# Microcontroller.net
KiCad netlist of a schematic drawn in Altium Designer
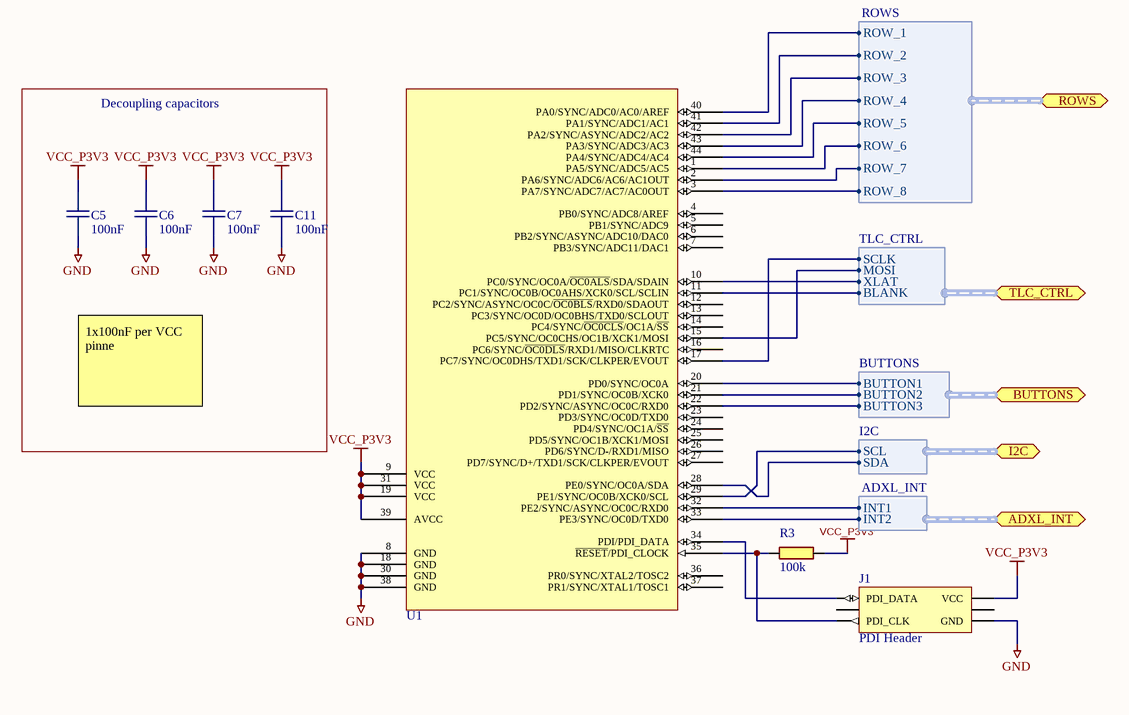
[diagram p0: Microcontroller.SchDoc]

(export (version "E")
  (design (tool "Eeschema 10.0.6"))
  (components
    (comp (ref "C5")
      (value "100nF")
      (footprint "CAPC0805(2012)100_N")
      (description "X7R 50V")
      (libsource (lib "OVLib") (part "CAP"))
    )
    (comp (ref "C6")
      (value "100nF")
      (footprint "CAPC0805(2012)100_N")
      (description "X7R 50V")
      (libsource (lib "OVLib") (part "CAP"))
    )
    (comp (ref "C7")
      (value "100nF")
      (footprint "CAPC0805(2012)100_N")
      (description "X7R 50V")
      (libsource (lib "OVLib") (part "CAP"))
    )
    (comp (ref "C11")
      (value "100nF")
      (footprint "CAPC0805(2012)100_N")
      (description "X7R 50V")
      (libsource (lib "OVLib") (part "CAP"))
    )
    (comp (ref "J1")
      (value "PDI Header")
      (footprint "HEADER_3x2")
      (description "PDI Xmega programming header")
      (libsource (lib "OVLib") (part "PDI-HEADER"))
    )
    (comp (ref "R3")
      (value "100k")
      (footprint "RESC0603(1608)_N")
      (description "0.1W 1% Thick film resistor")
      (libsource (lib "OVLib") (part "Resistor2"))
    )
    (comp (ref "U1")
      (value "ATXMEGA-A4U")
      (footprint "TQFP80P1200X1200X120-44N")
      (libsource (lib "OVLib") (part "ATXMEGA-A4U"))
    )
  )
  (nets
    (net (code "6") (name "/BLANK") (class "Default")
      (node (ref "U1") (pin "11") (pinfunction "PC1/SYNC/OC0B/OC0AHS/XCK0/SCL/SCLIN_11") (pintype "bidirectional"))
    )
    (net (code "7") (name "/BUTTON1") (class "Default")
      (node (ref "U1") (pin "20") (pinfunction "PD0/SYNC/OC0A_20") (pintype "bidirectional"))
    )
    (net (code "8") (name "/BUTTON2") (class "Default")
      (node (ref "U1") (pin "21") (pinfunction "PD1/SYNC/OC0B/XCK0_21") (pintype "bidirectional"))
    )
    (net (code "9") (name "/BUTTON3") (class "Default")
      (node (ref "U1") (pin "22") (pinfunction "PD2/SYNC/ASYNC/OC0C/RXD0_22") (pintype "bidirectional"))
    )
    (net (code "10") (name "/INT1") (class "Default")
      (node (ref "U1") (pin "32") (pinfunction "PE2/SYNC/ASYNC/OC0C/RXD0_32") (pintype "bidirectional"))
    )
    (net (code "11") (name "/INT2") (class "Default")
      (node (ref "U1") (pin "33") (pinfunction "PE3/SYNC/OC0D/TXD0_33") (pintype "bidirectional"))
    )
    (net (code "12") (name "/MOSI") (class "Default")
      (node (ref "U1") (pin "15") (pinfunction "PC5/SYNC/OC0CHS/OC1B/XCK1/MOSI_15") (pintype "bidirectional"))
    )
    (net (code "13") (name "/ROW_1") (class "Default")
      (node (ref "U1") (pin "40") (pinfunction "PA0/SYNC/ADC0/AC0/AREF_40") (pintype "bidirectional"))
    )
    (net (code "14") (name "/ROW_2") (class "Default")
      (node (ref "U1") (pin "41") (pinfunction "PA1/SYNC/ADC1/AC1_41") (pintype "bidirectional"))
    )
    (net (code "15") (name "/ROW_3") (class "Default")
      (node (ref "U1") (pin "42") (pinfunction "PA2/SYNC/ASYNC/ADC2/AC2_42") (pintype "bidirectional"))
    )
    (net (code "16") (name "/ROW_4") (class "Default")
      (node (ref "U1") (pin "43") (pinfunction "PA3/SYNC/ADC3/AC3_43") (pintype "bidirectional"))
    )
    (net (code "17") (name "/ROW_5") (class "Default")
      (node (ref "U1") (pin "44") (pinfunction "PA4/SYNC/ADC4/AC4_44") (pintype "bidirectional"))
    )
    (net (code "18") (name "/ROW_6") (class "Default")
      (node (ref "U1") (pin "1") (pinfunction "PA5/SYNC/ADC5/AC5_1") (pintype "bidirectional"))
    )
    (net (code "19") (name "/ROW_7") (class "Default")
      (node (ref "U1") (pin "2") (pinfunction "PA6/SYNC/ADC6/AC6/AC1OUT_2") (pintype "bidirectional"))
    )
    (net (code "20") (name "/ROW_8") (class "Default")
      (node (ref "U1") (pin "3") (pinfunction "PA7/SYNC/ADC7/AC7/AC0OUT_3") (pintype "bidirectional"))
    )
    (net (code "21") (name "/SCL") (class "Default")
      (node (ref "U1") (pin "29") (pinfunction "PE1/SYNC/OC0B/XCK0/SCL_29") (pintype "bidirectional"))
    )
    (net (code "22") (name "/SCLK") (class "Default")
      (node (ref "U1") (pin "17") (pinfunction "PC7/SYNC/OC0DHS/TXD1/SCK/CLKPER/EVOUT_17") (pintype "bidirectional"))
    )
    (net (code "23") (name "/SDA") (class "Default")
      (node (ref "U1") (pin "28") (pinfunction "PE0/SYNC/OC0A/SDA_28") (pintype "bidirectional"))
    )
    (net (code "24") (name "/XLAT") (class "Default")
      (node (ref "U1") (pin "10") (pinfunction "PC0/SYNC/OC0A/~{OC0ALS}/SDA/SDAIN_10") (pintype "bidirectional"))
    )
    (net (code "30") (name "GND") (class "Default")
      (node (ref "C11") (pin "1") (pinfunction "1_1") (pintype "passive"))
      (node (ref "C5") (pin "1") (pinfunction "1_1") (pintype "passive"))
      (node (ref "C6") (pin "1") (pinfunction "1_1") (pintype "passive"))
      (node (ref "C7") (pin "1") (pinfunction "1_1") (pintype "passive"))
      (node (ref "J1") (pin "6") (pinfunction "GND_6") (pintype "power_in"))
      (node (ref "U1") (pin "18") (pinfunction "GND_18") (pintype "power_in"))
      (node (ref "U1") (pin "30") (pinfunction "GND_30") (pintype "power_in"))
      (node (ref "U1") (pin "38") (pinfunction "GND_38") (pintype "power_in"))
      (node (ref "U1") (pin "8") (pinfunction "GND_8") (pintype "power_in"))
    )
    (net (code "31") (name "Net-(J1-PDI_CLK)") (class "Default")
      (node (ref "J1") (pin "5") (pinfunction "PDI_CLK_5") (pintype "output"))
      (node (ref "R3") (pin "2") (pinfunction "2_2") (pintype "passive"))
      (node (ref "U1") (pin "35") (pinfunction "~{RESET}/PDI_CLOCK_35") (pintype "input"))
    )
    (net (code "32") (name "Net-(J1-PDI_DATA)") (class "Default")
      (node (ref "J1") (pin "1") (pinfunction "PDI_DATA_1") (pintype "bidirectional"))
      (node (ref "U1") (pin "34") (pinfunction "PDI/PDI_DATA_34") (pintype "bidirectional"))
    )
    (net (code "33") (name "VCC_P3V3") (class "Default")
      (node (ref "C11") (pin "2") (pinfunction "2_2") (pintype "passive"))
      (node (ref "C5") (pin "2") (pinfunction "2_2") (pintype "passive"))
      (node (ref "C6") (pin "2") (pinfunction "2_2") (pintype "passive"))
      (node (ref "C7") (pin "2") (pinfunction "2_2") (pintype "passive"))
      (node (ref "J1") (pin "2") (pinfunction "VCC_2") (pintype "power_in"))
      (node (ref "R3") (pin "1") (pinfunction "1_1") (pintype "passive"))
      (node (ref "U1") (pin "19") (pinfunction "VCC_19") (pintype "power_in"))
      (node (ref "U1") (pin "31") (pinfunction "VCC_31") (pintype "power_in"))
      (node (ref "U1") (pin "39") (pinfunction "AVCC_39") (pintype "power_in"))
      (node (ref "U1") (pin "9") (pinfunction "VCC_9") (pintype "power_in"))
    )
    (net (code "34") (name "unconnected-(J1-Pad3)") (class "Default")
      (node (ref "J1") (pin "3") (pinfunction "3_3") (pintype "passive"))
    )
    (net (code "35") (name "unconnected-(J1-Pad4)") (class "Default")
      (node (ref "J1") (pin "4") (pinfunction "4_4") (pintype "passive"))
    )
    (net (code "36") (name "unconnected-(U1-PB0{slash}SYNC{slash}ADC8{slash}AREF-Pad4)") (class "Default")
      (node (ref "U1") (pin "4") (pinfunction "PB0/SYNC/ADC8/AREF_4") (pintype "bidirectional"))
    )
    (net (code "37") (name "unconnected-(U1-PB1{slash}SYNC{slash}ADC9-Pad5)") (class "Default")
      (node (ref "U1") (pin "5") (pinfunction "PB1/SYNC/ADC9_5") (pintype "bidirectional"))
    )
    (net (code "38") (name "unconnected-(U1-PB2{slash}SYNC{slash}ASYNC{slash}ADC10{slash}DAC0-Pad6)") (class "Default")
      (node (ref "U1") (pin "6") (pinfunction "PB2/SYNC/ASYNC/ADC10/DAC0_6") (pintype "bidirectional"))
    )
    (net (code "39") (name "unconnected-(U1-PB3{slash}SYNC{slash}ADC11{slash}DAC1-Pad7)") (class "Default")
      (node (ref "U1") (pin "7") (pinfunction "PB3/SYNC/ADC11/DAC1_7") (pintype "bidirectional"))
    )
    (net (code "40") (name "unconnected-(U1-PC2{slash}SYNC{slash}ASYNC{slash}OC0C{slash}~{OC0BLS}{slash}RXD0{slash}SDAOUT-Pad12)") (class "Default")
      (node (ref "U1") (pin "12") (pinfunction "PC2/SYNC/ASYNC/OC0C/~{OC0BLS}/RXD0/SDAOUT_12") (pintype "bidirectional"))
    )
    (net (code "41") (name "unconnected-(U1-PC3{slash}SYNC{slash}OC0D{slash}OC0BHS{slash}TXD0{slash}SCLOUT-Pad13)") (class "Default")
      (node (ref "U1") (pin "13") (pinfunction "PC3/SYNC/OC0D/OC0BHS/TXD0/SCLOUT_13") (pintype "bidirectional"))
    )
    (net (code "42") (name "unconnected-(U1-PC4{slash}SYNC{slash}~{OC0CLS}{slash}OC1A{slash}~{SS}-Pad14)") (class "Default")
      (node (ref "U1") (pin "14") (pinfunction "PC4/SYNC/~{OC0CLS}/OC1A/~{SS}_14") (pintype "bidirectional"))
    )
    (net (code "43") (name "unconnected-(U1-PC6{slash}SYNC{slash}~{OC0DLS}{slash}RXD1{slash}MISO{slash}CLKRTC-Pad16)") (class "Default")
      (node (ref "U1") (pin "16") (pinfunction "PC6/SYNC/~{OC0DLS}/RXD1/MISO/CLKRTC_16") (pintype "bidirectional"))
    )
    (net (code "44") (name "unconnected-(U1-PD3{slash}SYNC{slash}OC0D{slash}TXD0-Pad23)") (class "Default")
      (node (ref "U1") (pin "23") (pinfunction "PD3/SYNC/OC0D/TXD0_23") (pintype "bidirectional"))
    )
    (net (code "45") (name "unconnected-(U1-PD4{slash}SYNC{slash}OC1A{slash}~{SS}-Pad24)") (class "Default")
      (node (ref "U1") (pin "24") (pinfunction "PD4/SYNC/OC1A/~{SS}_24") (pintype "bidirectional"))
    )
    (net (code "46") (name "unconnected-(U1-PD5{slash}SYNC{slash}OC1B{slash}XCK1{slash}MOSI-Pad25)") (class "Default")
      (node (ref "U1") (pin "25") (pinfunction "PD5/SYNC/OC1B/XCK1/MOSI_25") (pintype "bidirectional"))
    )
    (net (code "47") (name "unconnected-(U1-PD6{slash}SYNC{slash}D-{slash}RXD1{slash}MISO-Pad26)") (class "Default")
      (node (ref "U1") (pin "26") (pinfunction "PD6/SYNC/D-/RXD1/MISO_26") (pintype "bidirectional"))
    )
    (net (code "48") (name "unconnected-(U1-PD7{slash}SYNC{slash}D+{slash}TXD1{slash}SCK{slash}CLKPER{slash}EVOUT-Pad27)") (class "Default")
      (node (ref "U1") (pin "27") (pinfunction "PD7/SYNC/D+/TXD1/SCK/CLKPER/EVOUT_27") (pintype "bidirectional"))
    )
    (net (code "49") (name "unconnected-(U1-PR0{slash}SYNC{slash}XTAL2{slash}TOSC2-Pad36)") (class "Default")
      (node (ref "U1") (pin "36") (pinfunction "PR0/SYNC/XTAL2/TOSC2_36") (pintype "bidirectional"))
    )
    (net (code "50") (name "unconnected-(U1-PR1{slash}SYNC{slash}XTAL1{slash}TOSC1-Pad37)") (class "Default")
      (node (ref "U1") (pin "37") (pinfunction "PR1/SYNC/XTAL1/TOSC1_37") (pintype "bidirectional"))
    )
  )
)
